# v6smd.net
KiCad netlist of a schematic drawn in EAGLE
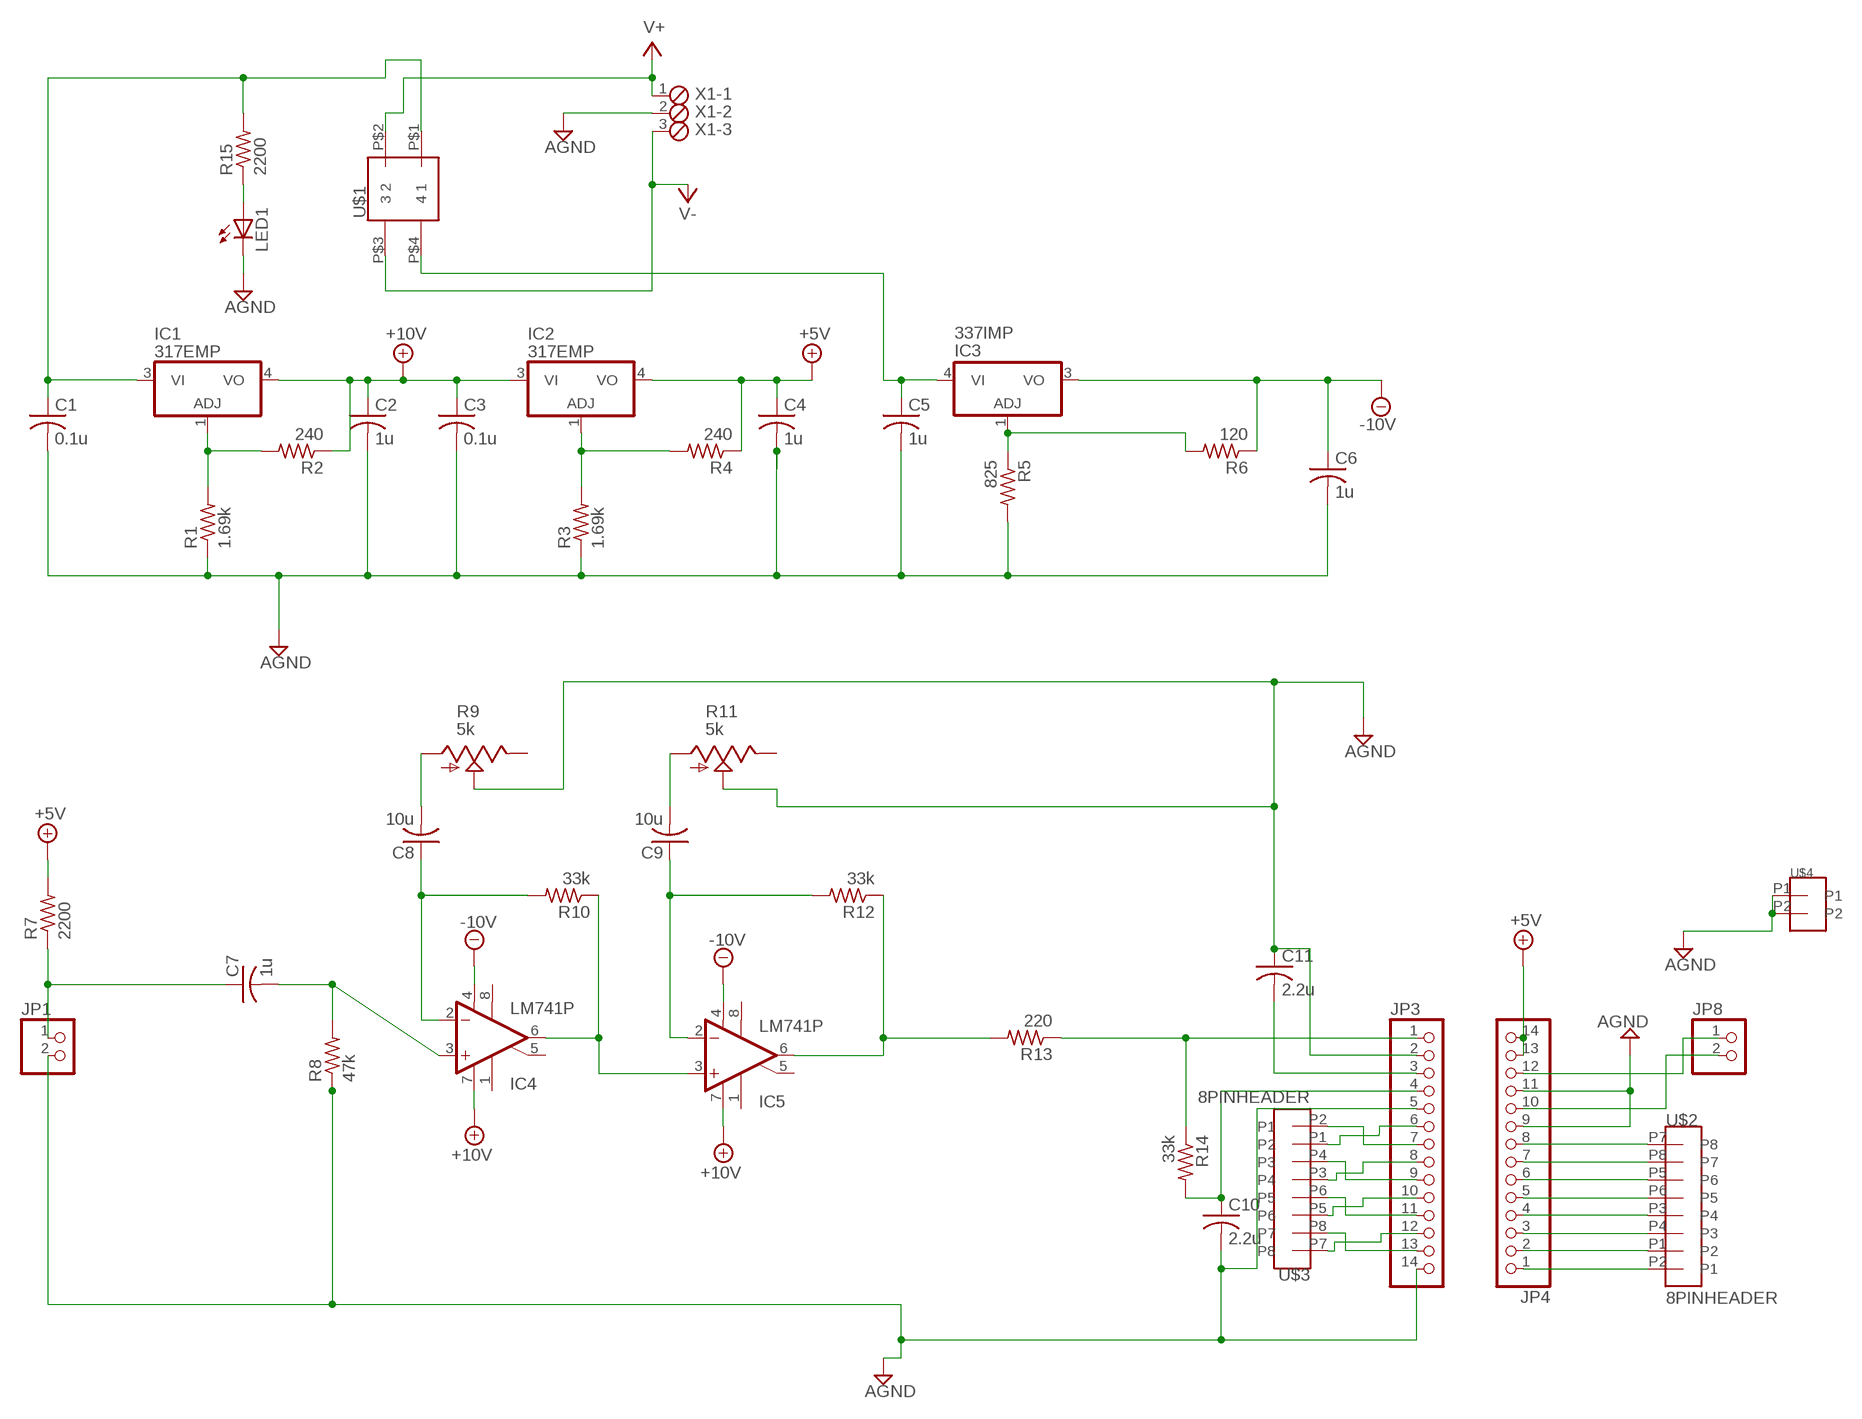
[diagram p0: schematic, sheet 1]

(export (version "E")
  (design (tool "Eeschema 10.0.6"))
  (components
    (comp (ref "C1")
      (value "0.1u")
      (footprint "eagle-import:C1206")
      (libsource (lib "eagle-import") (part "C-USC1206"))
    )
    (comp (ref "C2")
      (value "1u")
      (footprint "eagle-import:C1206")
      (libsource (lib "eagle-import") (part "C-USC1206"))
    )
    (comp (ref "C3")
      (value "0.1u")
      (footprint "eagle-import:C1206")
      (libsource (lib "eagle-import") (part "C-USC1206"))
    )
    (comp (ref "C4")
      (value "1u")
      (footprint "eagle-import:C1206")
      (libsource (lib "eagle-import") (part "C-USC1206"))
    )
    (comp (ref "C5")
      (value "1u")
      (footprint "eagle-import:C1206")
      (libsource (lib "eagle-import") (part "C-USC1206"))
    )
    (comp (ref "C6")
      (value "1u")
      (footprint "eagle-import:C1206")
      (libsource (lib "eagle-import") (part "C-USC1206"))
    )
    (comp (ref "C7")
      (value "1u")
      (footprint "eagle-import:C1206")
      (libsource (lib "eagle-import") (part "C-USC1206"))
    )
    (comp (ref "C8")
      (value "10u")
      (footprint "eagle-import:C1206")
      (libsource (lib "eagle-import") (part "C-USC1206"))
    )
    (comp (ref "C9")
      (value "10u")
      (footprint "eagle-import:C1206")
      (libsource (lib "eagle-import") (part "C-USC1206"))
    )
    (comp (ref "C10")
      (value "2.2u")
      (footprint "eagle-import:C1206")
      (libsource (lib "eagle-import") (part "C-USC1206"))
    )
    (comp (ref "C11")
      (value "2.2u")
      (footprint "eagle-import:C1206")
      (libsource (lib "eagle-import") (part "C-USC1206"))
    )
    (comp (ref "IC1")
      (value "317EMP")
      (footprint "eagle-import:SOT223")
      (libsource (lib "eagle-import") (part "317EMP"))
    )
    (comp (ref "IC2")
      (value "317EMP")
      (footprint "eagle-import:SOT223")
      (libsource (lib "eagle-import") (part "317EMP"))
    )
    (comp (ref "IC3")
      (value "337IMP")
      (footprint "eagle-import:SOT223")
      (libsource (lib "eagle-import") (part "337IMP"))
    )
    (comp (ref "IC4")
      (value "LM741P")
      (footprint "eagle-import:DIL08")
      (libsource (lib "eagle-import") (part "741PLM"))
    )
    (comp (ref "IC5")
      (value "LM741P")
      (footprint "eagle-import:DIL08")
      (libsource (lib "eagle-import") (part "741PLM"))
    )
    (comp (ref "JP1")
      (value "PINHD-1X2")
      (footprint "eagle-import:1X02")
      (libsource (lib "eagle-import") (part "PINHD-1X2"))
    )
    (comp (ref "JP3")
      (value "PINHD-1X14")
      (footprint "eagle-import:1X14")
      (libsource (lib "eagle-import") (part "PINHD-1X14"))
    )
    (comp (ref "JP4")
      (value "PINHD-1X14")
      (footprint "eagle-import:1X14")
      (libsource (lib "eagle-import") (part "PINHD-1X14"))
    )
    (comp (ref "JP8")
      (value "PINHD-1X2")
      (footprint "eagle-import:1X02")
      (libsource (lib "eagle-import") (part "PINHD-1X2"))
    )
    (comp (ref "LED1")
      (value "LED3MM")
      (footprint "eagle-import:LED3MM")
      (libsource (lib "eagle-import") (part "LED3MM"))
    )
    (comp (ref "R1")
      (value "1.69k")
      (footprint "eagle-import:R2512")
      (libsource (lib "eagle-import") (part "R-US_R2512"))
    )
    (comp (ref "R2")
      (value "240")
      (footprint "eagle-import:R2512")
      (libsource (lib "eagle-import") (part "R-US_R2512"))
    )
    (comp (ref "R3")
      (value "1.69k")
      (footprint "eagle-import:R2512")
      (libsource (lib "eagle-import") (part "R-US_R2512"))
    )
    (comp (ref "R4")
      (value "240")
      (footprint "eagle-import:R2512")
      (libsource (lib "eagle-import") (part "R-US_R2512"))
    )
    (comp (ref "R5")
      (value "825")
      (footprint "eagle-import:R2512")
      (libsource (lib "eagle-import") (part "R-US_R2512"))
    )
    (comp (ref "R6")
      (value "120")
      (footprint "eagle-import:R2512")
      (libsource (lib "eagle-import") (part "R-US_R2512"))
    )
    (comp (ref "R7")
      (value "2200")
      (footprint "eagle-import:R2512")
      (libsource (lib "eagle-import") (part "R-US_R2512"))
    )
    (comp (ref "R8")
      (value "47k")
      (footprint "eagle-import:R2512")
      (libsource (lib "eagle-import") (part "R-US_R2512"))
    )
    (comp (ref "R9")
      (value "5k")
      (footprint "eagle-import:B64Y")
      (libsource (lib "eagle-import") (part "TRIM_US-B64Y"))
    )
    (comp (ref "R10")
      (value "33k")
      (footprint "eagle-import:R2512")
      (libsource (lib "eagle-import") (part "R-US_R2512"))
    )
    (comp (ref "R11")
      (value "5k")
      (footprint "eagle-import:B64Y")
      (libsource (lib "eagle-import") (part "TRIM_US-B64Y"))
    )
    (comp (ref "R12")
      (value "33k")
      (footprint "eagle-import:R2512")
      (libsource (lib "eagle-import") (part "R-US_R2512"))
    )
    (comp (ref "R13")
      (value "220")
      (footprint "eagle-import:R2512")
      (libsource (lib "eagle-import") (part "R-US_R2512"))
    )
    (comp (ref "R14")
      (value "33k")
      (footprint "eagle-import:R2512")
      (libsource (lib "eagle-import") (part "R-US_R2512"))
    )
    (comp (ref "R15")
      (value "2200")
      (footprint "eagle-import:R2512")
      (libsource (lib "eagle-import") (part "R-US_R2512"))
    )
    (comp (ref "U$1")
      (value "S201031MS02Q")
      (footprint "eagle-import:DPST_FOOTPRINT")
      (libsource (lib "eagle-import") (part "S201031MS02Q"))
    )
    (comp (ref "U$2")
      (value "8PINHEADER")
      (footprint "eagle-import:2X4HEADER")
      (libsource (lib "eagle-import") (part "8PINHEADER"))
    )
    (comp (ref "U$3")
      (value "8PINHEADER")
      (footprint "eagle-import:2X4HEADER")
      (libsource (lib "eagle-import") (part "8PINHEADER"))
    )
    (comp (ref "U$4")
      (value "2X1HEADER")
      (footprint "eagle-import:2X1HEADER")
      (libsource (lib "eagle-import") (part "2X1HEADER"))
    )
    (comp (ref "X1")
      (value "MPT3")
      (footprint "eagle-import:3POL254")
      (libsource (lib "eagle-import") (part "MPT3"))
    )
  )
  (nets
    (net (code "1") (name "+5V") (class "Default")
      (node (ref "C4") (pin "1") (pinfunction "1_1") (pintype "passive"))
      (node (ref "IC2") (pin "4") (pinfunction "VO_4") (pintype "passive"))
      (node (ref "JP4") (pin "13") (pinfunction "13_13") (pintype "passive"))
      (node (ref "JP4") (pin "14") (pinfunction "14_14") (pintype "passive"))
      (node (ref "R4") (pin "1") (pinfunction "1_1") (pintype "passive"))
      (node (ref "R7") (pin "2") (pinfunction "2_2") (pintype "passive"))
    )
    (net (code "2") (name "+10V") (class "Default")
      (node (ref "C2") (pin "1") (pinfunction "1_1") (pintype "passive"))
      (node (ref "C3") (pin "1") (pinfunction "1_1") (pintype "passive"))
      (node (ref "IC1") (pin "4") (pinfunction "VO_4") (pintype "passive"))
      (node (ref "IC2") (pin "3") (pinfunction "VI_3") (pintype "input"))
      (node (ref "IC4") (pin "7") (pinfunction "V+_7") (pintype "power_in"))
      (node (ref "IC5") (pin "7") (pinfunction "V+_7") (pintype "power_in"))
      (node (ref "R2") (pin "1") (pinfunction "1_1") (pintype "passive"))
    )
    (net (code "3") (name "-10V") (class "Default")
      (node (ref "C6") (pin "1") (pinfunction "1_1") (pintype "passive"))
      (node (ref "IC3") (pin "3") (pinfunction "VO_3") (pintype "passive"))
      (node (ref "IC4") (pin "4") (pinfunction "V-_4") (pintype "power_in"))
      (node (ref "IC5") (pin "4") (pinfunction "V-_4") (pintype "power_in"))
      (node (ref "R6") (pin "1") (pinfunction "1_1") (pintype "passive"))
    )
    (net (code "4") (name "AGND") (class "Default")
      (node (ref "C1") (pin "2") (pinfunction "2_2") (pintype "passive"))
      (node (ref "C10") (pin "2") (pinfunction "2_2") (pintype "passive"))
      (node (ref "C11") (pin "1") (pinfunction "1_1") (pintype "passive"))
      (node (ref "C2") (pin "2") (pinfunction "2_2") (pintype "passive"))
      (node (ref "C3") (pin "2") (pinfunction "2_2") (pintype "passive"))
      (node (ref "C4") (pin "2") (pinfunction "2_2") (pintype "passive"))
      (node (ref "C5") (pin "2") (pinfunction "2_2") (pintype "passive"))
      (node (ref "C6") (pin "2") (pinfunction "2_2") (pintype "passive"))
      (node (ref "JP1") (pin "2") (pinfunction "2_2") (pintype "passive"))
      (node (ref "JP3") (pin "14") (pinfunction "14_14") (pintype "passive"))
      (node (ref "JP3") (pin "2") (pinfunction "2_2") (pintype "passive"))
      (node (ref "JP3") (pin "5") (pinfunction "5_5") (pintype "passive"))
      (node (ref "JP4") (pin "11") (pinfunction "11_11") (pintype "passive"))
      (node (ref "JP4") (pin "9") (pinfunction "9_9") (pintype "passive"))
      (node (ref "LED1") (pin "K") (pinfunction "C_K") (pintype "passive"))
      (node (ref "R1") (pin "1") (pinfunction "1_1") (pintype "passive"))
      (node (ref "R11") (pin "S") (pinfunction "S_S") (pintype "passive"))
      (node (ref "R3") (pin "1") (pinfunction "1_1") (pintype "passive"))
      (node (ref "R5") (pin "2") (pinfunction "2_2") (pintype "passive"))
      (node (ref "R8") (pin "1") (pinfunction "1_1") (pintype "passive"))
      (node (ref "R9") (pin "S") (pinfunction "S_S") (pintype "passive"))
      (node (ref "U$4") (pin "P1") (pinfunction "P1_P1") (pintype "bidirectional"))
      (node (ref "U$4") (pin "P2") (pinfunction "P2_P2") (pintype "bidirectional"))
      (node (ref "X1") (pin "2") (pinfunction "1_2") (pintype "passive"))
    )
    (net (code "5") (name "Net-(C7-Pad1)") (class "Default")
      (node (ref "C7") (pin "1") (pinfunction "1_1") (pintype "passive"))
      (node (ref "JP1") (pin "1") (pinfunction "1_1") (pintype "passive"))
      (node (ref "R7") (pin "1") (pinfunction "1_1") (pintype "passive"))
    )
    (net (code "6") (name "Net-(C8-Pad2)") (class "Default")
      (node (ref "C8") (pin "2") (pinfunction "2_2") (pintype "passive"))
      (node (ref "R9") (pin "A") (pinfunction "A_A") (pintype "passive"))
    )
    (net (code "7") (name "Net-(C9-Pad2)") (class "Default")
      (node (ref "C9") (pin "2") (pinfunction "2_2") (pintype "passive"))
      (node (ref "R11") (pin "A") (pinfunction "A_A") (pintype "passive"))
    )
    (net (code "8") (name "Net-(C10-Pad1)") (class "Default")
      (node (ref "C10") (pin "1") (pinfunction "1_1") (pintype "passive"))
      (node (ref "JP3") (pin "4") (pinfunction "4_4") (pintype "passive"))
      (node (ref "R14") (pin "2") (pinfunction "2_2") (pintype "passive"))
    )
    (net (code "9") (name "Net-(C11-Pad2)") (class "Default")
      (node (ref "C11") (pin "2") (pinfunction "2_2") (pintype "passive"))
      (node (ref "JP3") (pin "3") (pinfunction "3_3") (pintype "passive"))
    )
    (net (code "10") (name "Net-(IC1-ADJ)") (class "Default")
      (node (ref "IC1") (pin "1") (pinfunction "ADJ_1") (pintype "input"))
      (node (ref "R1") (pin "2") (pinfunction "2_2") (pintype "passive"))
      (node (ref "R2") (pin "2") (pinfunction "2_2") (pintype "passive"))
    )
    (net (code "11") (name "Net-(IC1-VI)") (class "Default")
      (node (ref "C1") (pin "1") (pinfunction "1_1") (pintype "passive"))
      (node (ref "IC1") (pin "3") (pinfunction "VI_3") (pintype "input"))
      (node (ref "R15") (pin "2") (pinfunction "2_2") (pintype "passive"))
      (node (ref "U$1") (pin "P$1") (pinfunction "1_P$1") (pintype "bidirectional"))
    )
    (net (code "12") (name "Net-(IC2-ADJ)") (class "Default")
      (node (ref "IC2") (pin "1") (pinfunction "ADJ_1") (pintype "input"))
      (node (ref "R3") (pin "2") (pinfunction "2_2") (pintype "passive"))
      (node (ref "R4") (pin "2") (pinfunction "2_2") (pintype "passive"))
    )
    (net (code "13") (name "Net-(IC3-ADJ)") (class "Default")
      (node (ref "IC3") (pin "1") (pinfunction "ADJ_1") (pintype "input"))
      (node (ref "R5") (pin "1") (pinfunction "1_1") (pintype "passive"))
      (node (ref "R6") (pin "2") (pinfunction "2_2") (pintype "passive"))
    )
    (net (code "14") (name "Net-(IC3-VI)") (class "Default")
      (node (ref "C5") (pin "1") (pinfunction "1_1") (pintype "passive"))
      (node (ref "IC3") (pin "4") (pinfunction "VI_4") (pintype "input"))
      (node (ref "U$1") (pin "P$4") (pinfunction "4_P$4") (pintype "bidirectional"))
    )
    (net (code "15") (name "Net-(IC4-+IN)") (class "Default")
      (node (ref "C7") (pin "2") (pinfunction "2_2") (pintype "passive"))
      (node (ref "IC4") (pin "3") (pinfunction "+IN_3") (pintype "input"))
      (node (ref "R8") (pin "2") (pinfunction "2_2") (pintype "passive"))
    )
    (net (code "16") (name "Net-(IC4--IN)") (class "Default")
      (node (ref "C8") (pin "1") (pinfunction "1_1") (pintype "passive"))
      (node (ref "IC4") (pin "2") (pinfunction "-IN_2") (pintype "input"))
      (node (ref "R10") (pin "2") (pinfunction "2_2") (pintype "passive"))
    )
    (net (code "17") (name "Net-(IC4-OUT)") (class "Default")
      (node (ref "IC4") (pin "6") (pinfunction "OUT_6") (pintype "output"))
      (node (ref "IC5") (pin "3") (pinfunction "+IN_3") (pintype "input"))
      (node (ref "R10") (pin "1") (pinfunction "1_1") (pintype "passive"))
    )
    (net (code "18") (name "Net-(IC5--IN)") (class "Default")
      (node (ref "C9") (pin "1") (pinfunction "1_1") (pintype "passive"))
      (node (ref "IC5") (pin "2") (pinfunction "-IN_2") (pintype "input"))
      (node (ref "R12") (pin "2") (pinfunction "2_2") (pintype "passive"))
    )
    (net (code "19") (name "Net-(IC5-OUT)") (class "Default")
      (node (ref "IC5") (pin "6") (pinfunction "OUT_6") (pintype "output"))
      (node (ref "R12") (pin "1") (pinfunction "1_1") (pintype "passive"))
      (node (ref "R13") (pin "2") (pinfunction "2_2") (pintype "passive"))
    )
    (net (code "20") (name "Net-(JP3-Pad1)") (class "Default")
      (node (ref "JP3") (pin "1") (pinfunction "1_1") (pintype "passive"))
      (node (ref "R13") (pin "1") (pinfunction "1_1") (pintype "passive"))
      (node (ref "R14") (pin "1") (pinfunction "1_1") (pintype "passive"))
    )
    (net (code "21") (name "Net-(JP4-Pad10)") (class "Default")
      (node (ref "JP4") (pin "10") (pinfunction "10_10") (pintype "passive"))
      (node (ref "JP8") (pin "2") (pinfunction "2_2") (pintype "passive"))
    )
    (net (code "22") (name "Net-(JP4-Pad12)") (class "Default")
      (node (ref "JP4") (pin "12") (pinfunction "12_12") (pintype "passive"))
      (node (ref "JP8") (pin "1") (pinfunction "1_1") (pintype "passive"))
    )
    (net (code "23") (name "Net-(LED1-PadA)") (class "Default")
      (node (ref "LED1") (pin "A") (pinfunction "A_A") (pintype "passive"))
      (node (ref "R15") (pin "1") (pinfunction "1_1") (pintype "passive"))
    )
    (net (code "24") (name "Net-(U$2-P1)") (class "Default")
      (node (ref "JP4") (pin "1") (pinfunction "1_1") (pintype "passive"))
      (node (ref "U$2") (pin "P2") (pinfunction "P1_P2") (pintype "bidirectional"))
    )
    (net (code "25") (name "Net-(U$2-P2)") (class "Default")
      (node (ref "JP4") (pin "2") (pinfunction "2_2") (pintype "passive"))
      (node (ref "U$2") (pin "P1") (pinfunction "P2_P1") (pintype "bidirectional"))
    )
    (net (code "26") (name "Net-(U$2-P3)") (class "Default")
      (node (ref "JP4") (pin "3") (pinfunction "3_3") (pintype "passive"))
      (node (ref "U$2") (pin "P4") (pinfunction "P3_P4") (pintype "bidirectional"))
    )
    (net (code "27") (name "Net-(U$2-P4)") (class "Default")
      (node (ref "JP4") (pin "4") (pinfunction "4_4") (pintype "passive"))
      (node (ref "U$2") (pin "P3") (pinfunction "P4_P3") (pintype "bidirectional"))
    )
    (net (code "28") (name "Net-(U$2-P5)") (class "Default")
      (node (ref "JP4") (pin "5") (pinfunction "5_5") (pintype "passive"))
      (node (ref "U$2") (pin "P6") (pinfunction "P5_P6") (pintype "bidirectional"))
    )
    (net (code "29") (name "Net-(U$2-P6)") (class "Default")
      (node (ref "JP4") (pin "6") (pinfunction "6_6") (pintype "passive"))
      (node (ref "U$2") (pin "P5") (pinfunction "P6_P5") (pintype "bidirectional"))
    )
    (net (code "30") (name "Net-(U$2-P7)") (class "Default")
      (node (ref "JP4") (pin "7") (pinfunction "7_7") (pintype "passive"))
      (node (ref "U$2") (pin "P8") (pinfunction "P7_P8") (pintype "bidirectional"))
    )
    (net (code "31") (name "Net-(U$2-P8)") (class "Default")
      (node (ref "JP4") (pin "8") (pinfunction "8_8") (pintype "passive"))
      (node (ref "U$2") (pin "P7") (pinfunction "P8_P7") (pintype "bidirectional"))
    )
    (net (code "32") (name "Net-(U$3-P1)") (class "Default")
      (node (ref "JP3") (pin "7") (pinfunction "7_7") (pintype "passive"))
      (node (ref "U$3") (pin "P2") (pinfunction "P1_P2") (pintype "bidirectional"))
    )
    (net (code "33") (name "Net-(U$3-P2)") (class "Default")
      (node (ref "JP3") (pin "6") (pinfunction "6_6") (pintype "passive"))
      (node (ref "U$3") (pin "P1") (pinfunction "P2_P1") (pintype "bidirectional"))
    )
    (net (code "34") (name "Net-(U$3-P3)") (class "Default")
      (node (ref "JP3") (pin "9") (pinfunction "9_9") (pintype "passive"))
      (node (ref "U$3") (pin "P4") (pinfunction "P3_P4") (pintype "bidirectional"))
    )
    (net (code "35") (name "Net-(U$3-P4)") (class "Default")
      (node (ref "JP3") (pin "8") (pinfunction "8_8") (pintype "passive"))
      (node (ref "U$3") (pin "P3") (pinfunction "P4_P3") (pintype "bidirectional"))
    )
    (net (code "36") (name "Net-(U$3-P5)") (class "Default")
      (node (ref "JP3") (pin "11") (pinfunction "11_11") (pintype "passive"))
      (node (ref "U$3") (pin "P6") (pinfunction "P5_P6") (pintype "bidirectional"))
    )
    (net (code "37") (name "Net-(U$3-P6)") (class "Default")
      (node (ref "JP3") (pin "10") (pinfunction "10_10") (pintype "passive"))
      (node (ref "U$3") (pin "P5") (pinfunction "P6_P5") (pintype "bidirectional"))
    )
    (net (code "38") (name "Net-(U$3-P7)") (class "Default")
      (node (ref "JP3") (pin "13") (pinfunction "13_13") (pintype "passive"))
      (node (ref "U$3") (pin "P8") (pinfunction "P7_P8") (pintype "bidirectional"))
    )
    (net (code "39") (name "Net-(U$3-P8)") (class "Default")
      (node (ref "JP3") (pin "12") (pinfunction "12_12") (pintype "passive"))
      (node (ref "U$3") (pin "P7") (pinfunction "P8_P7") (pintype "bidirectional"))
    )
    (net (code "40") (name "V+") (class "Default")
      (node (ref "U$1") (pin "P$2") (pinfunction "2_P$2") (pintype "bidirectional"))
      (node (ref "X1") (pin "1") (pinfunction "1_1") (pintype "passive"))
    )
    (net (code "41") (name "V-") (class "Default")
      (node (ref "U$1") (pin "P$3") (pinfunction "3_P$3") (pintype "bidirectional"))
      (node (ref "X1") (pin "3") (pinfunction "1_3") (pintype "passive"))
    )
    (net (code "42") (name "unconnected-(IC4-ON1-Pad1)") (class "Default")
      (node (ref "IC4") (pin "1") (pinfunction "ON1_1") (pintype "passive"))
    )
    (net (code "43") (name "unconnected-(IC4-ON2-Pad5)") (class "Default")
      (node (ref "IC4") (pin "5") (pinfunction "ON2_5") (pintype "passive"))
    )
    (net (code "44") (name "unconnected-(IC4-OPT-Pad8)") (class "Default")
      (node (ref "IC4") (pin "8") (pinfunction "OPT_8") (pintype "passive"))
    )
    (net (code "45") (name "unconnected-(IC5-ON1-Pad1)") (class "Default")
      (node (ref "IC5") (pin "1") (pinfunction "ON1_1") (pintype "passive"))
    )
    (net (code "46") (name "unconnected-(IC5-ON2-Pad5)") (class "Default")
      (node (ref "IC5") (pin "5") (pinfunction "ON2_5") (pintype "passive"))
    )
    (net (code "47") (name "unconnected-(IC5-OPT-Pad8)") (class "Default")
      (node (ref "IC5") (pin "8") (pinfunction "OPT_8") (pintype "passive"))
    )
    (net (code "48") (name "unconnected-(R9-PadE)") (class "Default")
      (node (ref "R9") (pin "E") (pinfunction "E_E") (pintype "passive"))
    )
    (net (code "49") (name "unconnected-(R11-PadE)") (class "Default")
      (node (ref "R11") (pin "E") (pinfunction "E_E") (pintype "passive"))
    )
  )
)
